# charge_controller_mk2.net
KiCad netlist of a schematic drawn in EAGLE
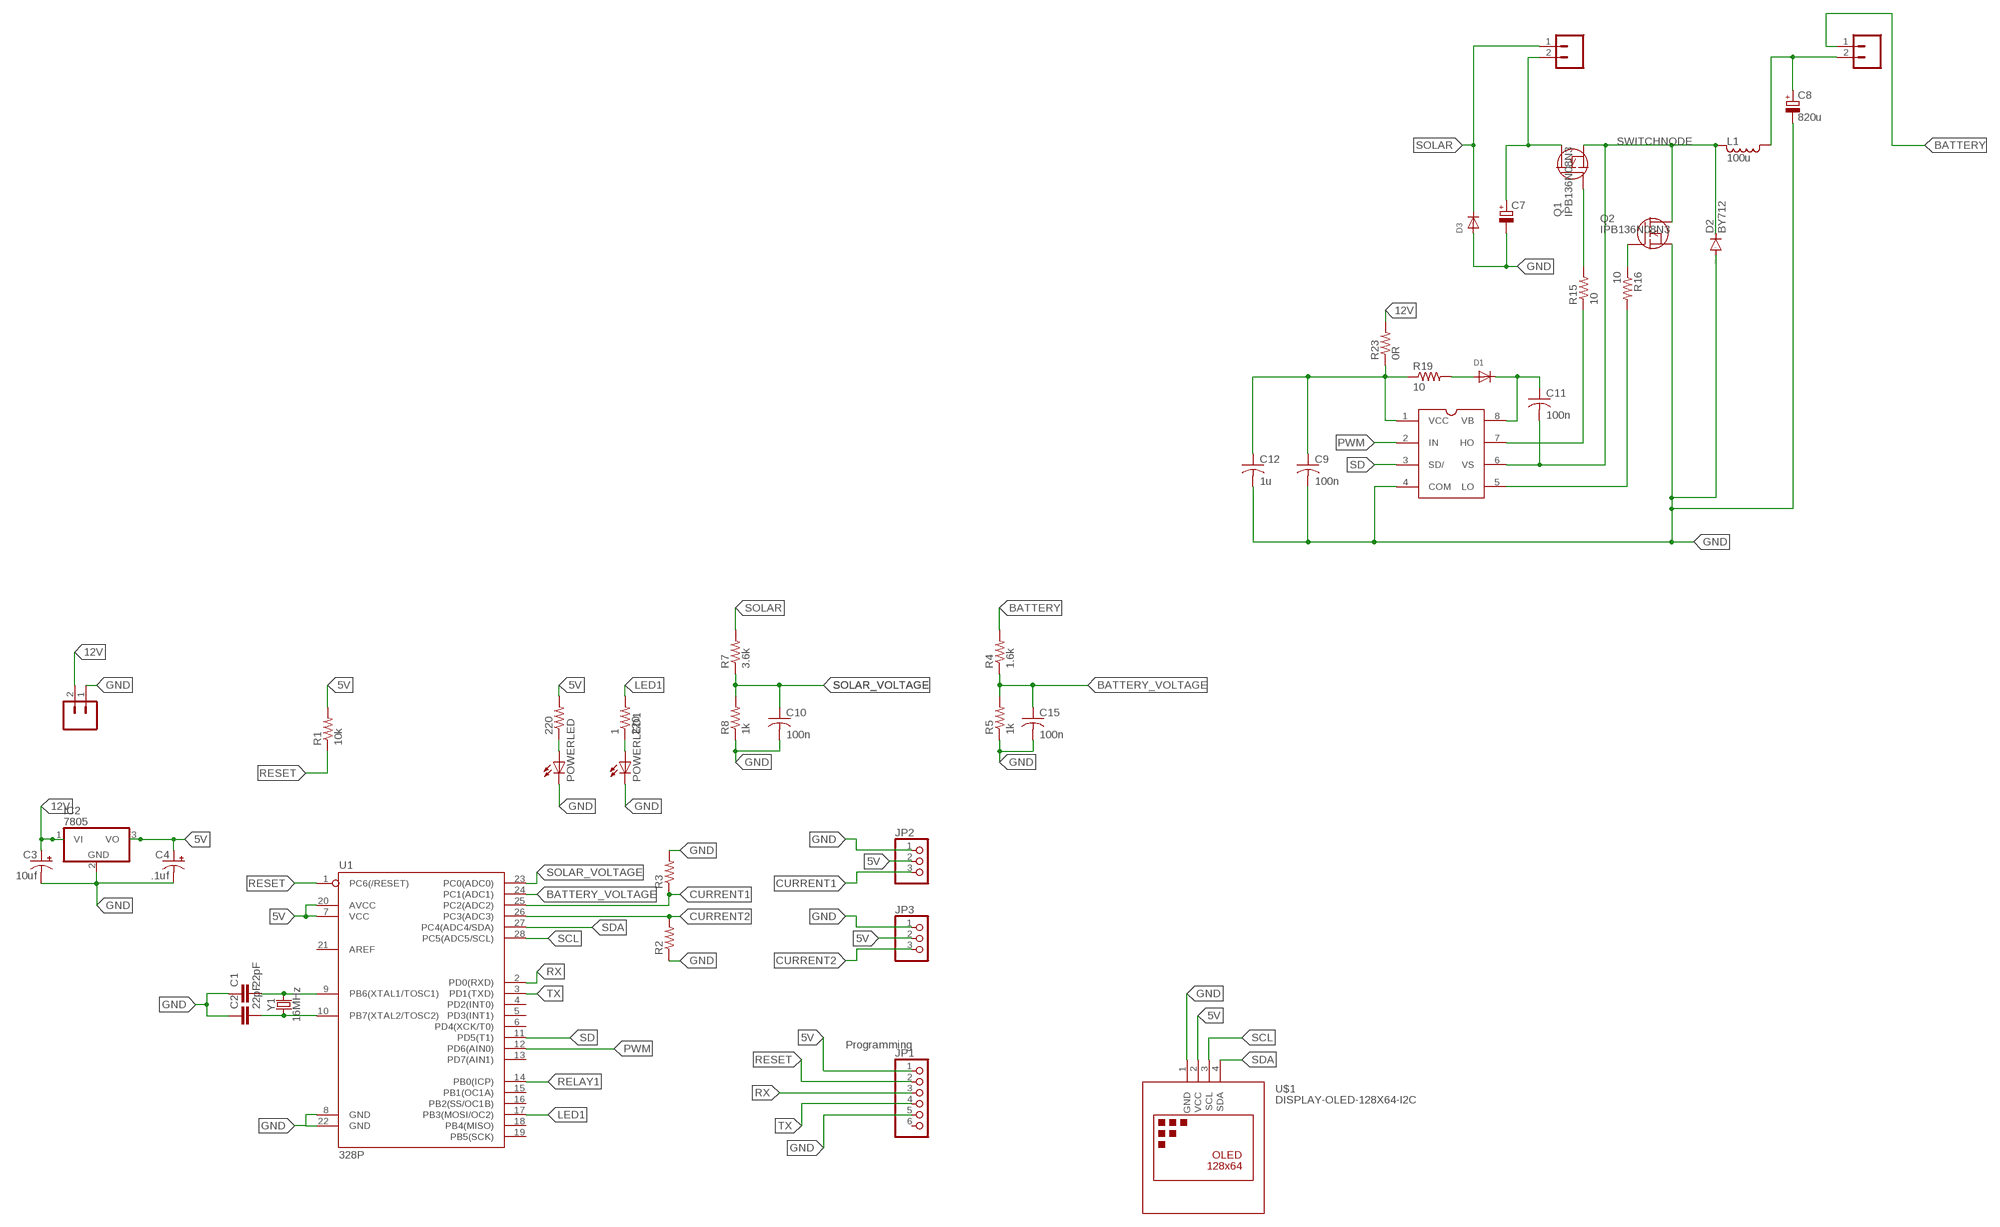
[diagram p0: schematic, sheet 1]

(export (version "E")
  (design (tool "Eeschema 10.0.6"))
  (components
    (comp (ref "1")
      (value "220")
      (footprint "eagle-import:0204_5")
      (libsource (lib "eagle-import") (part "adafruit_420_R-US_0204/5"))
    )
    (comp (ref "220")
      (value "R-US_0204/5")
      (footprint "eagle-import:0204_5")
      (libsource (lib "eagle-import") (part "adafruit_420_R-US_0204/5"))
    )
    (comp (ref "BATTERY-OUT")
      (value "CONN_025MM")
      (footprint "eagle-import:SCREWTERMINAL-5MM-2")
      (libsource (lib "eagle-import") (part "CONN_025MM"))
    )
    (comp (ref "C1")
      (value "22pF")
      (footprint "eagle-import:CAP-PTH-2.54")
      (libsource (lib "eagle-import") (part "22PF-PTH-2.54MM-200V-5%"))
    )
    (comp (ref "C2")
      (value "22pF")
      (footprint "eagle-import:CAP-PTH-2.54")
      (libsource (lib "eagle-import") (part "22PF-PTH-2.54MM-200V-5%"))
    )
    (comp (ref "C3")
      (value "10uf")
      (footprint "eagle-import:E5-5")
      (libsource (lib "eagle-import") (part "CPOL-USE5-5"))
    )
    (comp (ref "C4")
      (value ".1uf")
      (footprint "eagle-import:E5-5")
      (libsource (lib "eagle-import") (part "CPOL-USE5-5"))
    )
    (comp (ref "C7")
      (value "680u")
      (footprint "eagle-import:10MM")
      (libsource (lib "eagle-import") (part "C_POLARIZED10MM"))
    )
    (comp (ref "C8")
      (value "820u")
      (footprint "eagle-import:10MM")
      (libsource (lib "eagle-import") (part "C_POLARIZED10MM"))
    )
    (comp (ref "C9")
      (value "100n")
      (footprint "eagle-import:C050-025X075")
      (libsource (lib "eagle-import") (part "C-US050-025X075"))
    )
    (comp (ref "C10")
      (value "100n")
      (footprint "eagle-import:C050-025X075")
      (libsource (lib "eagle-import") (part "C-US050-025X075"))
    )
    (comp (ref "C11")
      (value "100n")
      (footprint "eagle-import:C050-055X075")
      (libsource (lib "eagle-import") (part "C-US050-055X075"))
    )
    (comp (ref "C12")
      (value "1u")
      (footprint "eagle-import:C050-025X075")
      (libsource (lib "eagle-import") (part "C-US050-025X075"))
    )
    (comp (ref "C15")
      (value "100n")
      (footprint "eagle-import:C050-025X075")
      (libsource (lib "eagle-import") (part "C-US050-025X075"))
    )
    (comp (ref "D1")
      (value "DIODEDO-1N4148")
      (footprint "eagle-import:DO-1N4148")
      (libsource (lib "eagle-import") (part "DIODEDO-1N4148"))
    )
    (comp (ref "D2")
      (value "BY712")
      (footprint "eagle-import:SOD61E")
      (libsource (lib "eagle-import") (part "BY712"))
    )
    (comp (ref "D3")
      (value "DIODEDO-1N4148")
      (footprint "eagle-import:DO-1N4148")
      (libsource (lib "eagle-import") (part "DIODEDO-1N4148"))
    )
    (comp (ref "IC2")
      (value "7805")
      (footprint "eagle-import:TO220V")
      (libsource (lib "eagle-import") (part "78TV18"))
    )
    (comp (ref "J1")
      (value "PWR_in")
      (footprint "eagle-import:SCREWTERMINAL-5MM-2")
      (libsource (lib "eagle-import") (part "CONN_025MM"))
    )
    (comp (ref "JP1")
      (value "PINHD-1X6")
      (footprint "eagle-import:1X06")
      (libsource (lib "eagle-import") (part "PINHD-1X6"))
    )
    (comp (ref "JP2")
      (value "PINHD-1X3")
      (footprint "eagle-import:1X03")
      (libsource (lib "eagle-import") (part "PINHD-1X3"))
    )
    (comp (ref "JP3")
      (value "PINHD-1X3")
      (footprint "eagle-import:1X03")
      (libsource (lib "eagle-import") (part "PINHD-1X3"))
    )
    (comp (ref "L1")
      (value "100u")
      (footprint "eagle-import:MSS1583")
      (libsource (lib "eagle-import") (part "INDUCTORMSS1583"))
    )
    (comp (ref "POWERLED")
      (value "LED5MM")
      (footprint "eagle-import:LED5MM")
      (libsource (lib "eagle-import") (part "LED5MM"))
    )
    (comp (ref "POWERLED1")
      (value "LED5MM")
      (footprint "eagle-import:LED5MM")
      (libsource (lib "eagle-import") (part "LED5MM"))
    )
    (comp (ref "Q1")
      (value "IPB136N08N3")
      (footprint "eagle-import:TO220")
      (libsource (lib "eagle-import") (part "IRF840"))
    )
    (comp (ref "Q2")
      (value "IPB136N08N3")
      (footprint "eagle-import:TO220")
      (libsource (lib "eagle-import") (part "IRF840"))
    )
    (comp (ref "R1")
      (value "10k")
      (footprint "eagle-import:0204_5")
      (libsource (lib "eagle-import") (part "adafruit_420_R-US_0204/5"))
    )
    (comp (ref "R2")
      (value "R-US_0207/7")
      (footprint "eagle-import:0207_7")
      (libsource (lib "eagle-import") (part "R-US_0207/7"))
    )
    (comp (ref "R3")
      (value "R-US_0207/7")
      (footprint "eagle-import:0207_7")
      (libsource (lib "eagle-import") (part "R-US_0207/7"))
    )
    (comp (ref "R4")
      (value "1.6k")
      (footprint "eagle-import:0207_7")
      (libsource (lib "eagle-import") (part "R-US_0207/7"))
    )
    (comp (ref "R5")
      (value "1k")
      (footprint "eagle-import:0207_7")
      (libsource (lib "eagle-import") (part "R-US_0207/7"))
    )
    (comp (ref "R7")
      (value "3.6k")
      (footprint "eagle-import:0207_7")
      (libsource (lib "eagle-import") (part "R-US_0207/7"))
    )
    (comp (ref "R8")
      (value "1k")
      (footprint "eagle-import:0207_7")
      (libsource (lib "eagle-import") (part "R-US_0207/7"))
    )
    (comp (ref "R15")
      (value "10")
      (footprint "eagle-import:0204_7")
      (libsource (lib "eagle-import") (part "adafruit_420_R-US_0204/7"))
    )
    (comp (ref "R16")
      (value "10")
      (footprint "eagle-import:0204_7")
      (libsource (lib "eagle-import") (part "adafruit_420_R-US_0204/7"))
    )
    (comp (ref "R19")
      (value "10")
      (footprint "eagle-import:0204_7")
      (libsource (lib "eagle-import") (part "adafruit_420_R-US_0204/7"))
    )
    (comp (ref "R23")
      (value "0R")
      (footprint "eagle-import:0204_7")
      (libsource (lib "eagle-import") (part "adafruit_420_R-US_0204/7"))
    )
    (comp (ref "SOLAR-IN")
      (value "CONN_025MM")
      (footprint "eagle-import:SCREWTERMINAL-5MM-2")
      (libsource (lib "eagle-import") (part "CONN_025MM"))
    )
    (comp (ref "U$1")
      (value "DISPLAY-OLED-128X64-I2C")
      (footprint "eagle-import:DISPLAY-OLED-128X64-I2C")
      (libsource (lib "eagle-import") (part "DISPLAY-OLED-128X64-I2C"))
    )
    (comp (ref "U$2")
      (value "IR2104")
      (footprint "eagle-import:IR2104")
      (libsource (lib "eagle-import") (part "IR2104"))
    )
    (comp (ref "U1")
      (value "328P")
      (footprint "eagle-import:DIP28")
      (libsource (lib "eagle-import") (part "ATMEGA328P_PDIP"))
    )
    (comp (ref "Y1")
      (value "16MHz")
      (footprint "eagle-import:HC49US")
      (libsource (lib "eagle-import") (part "CRYSTAL-16MHZPTH-HC49US"))
    )
  )
  (nets
    (net (code "1") (name "/SWITCHNODE") (class "Default")
      (node (ref "C11") (pin "2") (pinfunction "2_2") (pintype "passive"))
      (node (ref "D2") (pin "C") (pinfunction "C_C") (pintype "passive"))
      (node (ref "L1") (pin "2") (pinfunction "2_2") (pintype "passive"))
      (node (ref "Q1") (pin "3") (pinfunction "S_3") (pintype "passive"))
      (node (ref "Q2") (pin "2") (pinfunction "D_2") (pintype "passive"))
      (node (ref "U$2") (pin "6") (pinfunction "VS_6") (pintype "power_in"))
    )
    (net (code "2") (name "5V") (class "Default")
      (node (ref "220") (pin "2") (pinfunction "2_2") (pintype "passive"))
      (node (ref "C4") (pin "+") (pinfunction "+_+") (pintype "passive"))
      (node (ref "IC2") (pin "3") (pinfunction "VO_3") (pintype "passive"))
      (node (ref "JP1") (pin "1") (pinfunction "1_1") (pintype "passive"))
      (node (ref "JP2") (pin "2") (pinfunction "2_2") (pintype "passive"))
      (node (ref "JP3") (pin "2") (pinfunction "2_2") (pintype "passive"))
      (node (ref "R1") (pin "2") (pinfunction "2_2") (pintype "passive"))
      (node (ref "U$1") (pin "2") (pinfunction "VCC_2") (pintype "power_in"))
      (node (ref "U1") (pin "20") (pinfunction "AVCC_20") (pintype "bidirectional"))
      (node (ref "U1") (pin "7") (pinfunction "VCC_7") (pintype "bidirectional"))
    )
    (net (code "3") (name "12V") (class "Default")
      (node (ref "C3") (pin "+") (pinfunction "+_+") (pintype "passive"))
      (node (ref "IC2") (pin "1") (pinfunction "VI_1") (pintype "input"))
      (node (ref "J1") (pin "2") (pinfunction "2_2") (pintype "passive"))
      (node (ref "R23") (pin "2") (pinfunction "2_2") (pintype "passive"))
    )
    (net (code "4") (name "BATTERY") (class "Default")
      (node (ref "BATTERY-OUT") (pin "1") (pinfunction "1_1") (pintype "passive"))
      (node (ref "R4") (pin "2") (pinfunction "2_2") (pintype "passive"))
    )
    (net (code "5") (name "BATTERY_VOLTAGE") (class "Default")
      (node (ref "C15") (pin "1") (pinfunction "1_1") (pintype "passive"))
      (node (ref "R4") (pin "1") (pinfunction "1_1") (pintype "passive"))
      (node (ref "R5") (pin "2") (pinfunction "2_2") (pintype "passive"))
      (node (ref "U1") (pin "24") (pinfunction "PC1(ADC1)_24") (pintype "bidirectional"))
    )
    (net (code "6") (name "CURRENT1") (class "Default")
      (node (ref "JP2") (pin "3") (pinfunction "3_3") (pintype "passive"))
      (node (ref "R3") (pin "1") (pinfunction "1_1") (pintype "passive"))
      (node (ref "U1") (pin "25") (pinfunction "PC2(ADC2)_25") (pintype "bidirectional"))
    )
    (net (code "7") (name "CURRENT2") (class "Default")
      (node (ref "JP3") (pin "3") (pinfunction "3_3") (pintype "passive"))
      (node (ref "R2") (pin "2") (pinfunction "2_2") (pintype "passive"))
      (node (ref "U1") (pin "26") (pinfunction "PC3(ADC3)_26") (pintype "bidirectional"))
    )
    (net (code "8") (name "GND") (class "Default")
      (node (ref "C1") (pin "1") (pinfunction "1_1") (pintype "passive"))
      (node (ref "C10") (pin "2") (pinfunction "2_2") (pintype "passive"))
      (node (ref "C12") (pin "2") (pinfunction "2_2") (pintype "passive"))
      (node (ref "C15") (pin "2") (pinfunction "2_2") (pintype "passive"))
      (node (ref "C2") (pin "1") (pinfunction "1_1") (pintype "passive"))
      (node (ref "C3") (pin "-") (pinfunction "-_-") (pintype "passive"))
      (node (ref "C4") (pin "-") (pinfunction "-_-") (pintype "passive"))
      (node (ref "C7") (pin "-") (pinfunction "-_-") (pintype "passive"))
      (node (ref "C8") (pin "-") (pinfunction "-_-") (pintype "passive"))
      (node (ref "C9") (pin "2") (pinfunction "2_2") (pintype "passive"))
      (node (ref "D2") (pin "A") (pinfunction "A_A") (pintype "passive"))
      (node (ref "D3") (pin "A") (pinfunction "A_A") (pintype "passive"))
      (node (ref "IC2") (pin "2") (pinfunction "GND_2") (pintype "passive"))
      (node (ref "J1") (pin "1") (pinfunction "1_1") (pintype "passive"))
      (node (ref "JP1") (pin "5") (pinfunction "5_5") (pintype "passive"))
      (node (ref "JP2") (pin "1") (pinfunction "1_1") (pintype "passive"))
      (node (ref "JP3") (pin "1") (pinfunction "1_1") (pintype "passive"))
      (node (ref "POWERLED") (pin "K") (pinfunction "C_K") (pintype "passive"))
      (node (ref "POWERLED1") (pin "K") (pinfunction "C_K") (pintype "passive"))
      (node (ref "Q2") (pin "3") (pinfunction "S_3") (pintype "passive"))
      (node (ref "R2") (pin "1") (pinfunction "1_1") (pintype "passive"))
      (node (ref "R3") (pin "2") (pinfunction "2_2") (pintype "passive"))
      (node (ref "R5") (pin "1") (pinfunction "1_1") (pintype "passive"))
      (node (ref "R8") (pin "1") (pinfunction "1_1") (pintype "passive"))
      (node (ref "U$1") (pin "1") (pinfunction "GND_1") (pintype "power_in"))
      (node (ref "U$2") (pin "4") (pinfunction "COM_4") (pintype "bidirectional"))
      (node (ref "U1") (pin "22") (pinfunction "GND_22") (pintype "bidirectional"))
      (node (ref "U1") (pin "8") (pinfunction "GND_8") (pintype "bidirectional"))
    )
    (net (code "9") (name "LED1") (class "Default")
      (node (ref "1") (pin "2") (pinfunction "2_2") (pintype "passive"))
      (node (ref "U1") (pin "17") (pinfunction "PB3(MOSI/OC2)_17") (pintype "bidirectional"))
    )
    (net (code "10") (name "Net-(1-Pad1)") (class "Default")
      (node (ref "1") (pin "1") (pinfunction "1_1") (pintype "passive"))
      (node (ref "POWERLED1") (pin "A") (pinfunction "A_A") (pintype "passive"))
    )
    (net (code "11") (name "Net-(220-Pad1)") (class "Default")
      (node (ref "220") (pin "1") (pinfunction "1_1") (pintype "passive"))
      (node (ref "POWERLED") (pin "A") (pinfunction "A_A") (pintype "passive"))
    )
    (net (code "12") (name "Net-(BATTERY-OUT-Pad2)") (class "Default")
      (node (ref "BATTERY-OUT") (pin "2") (pinfunction "2_2") (pintype "passive"))
      (node (ref "C8") (pin "+") (pinfunction "+_+") (pintype "passive"))
      (node (ref "L1") (pin "1") (pinfunction "1_1") (pintype "passive"))
    )
    (net (code "13") (name "Net-(D1-PadA)") (class "Default")
      (node (ref "D1") (pin "A") (pinfunction "A_A") (pintype "passive"))
      (node (ref "R19") (pin "2") (pinfunction "2_2") (pintype "passive"))
    )
    (net (code "14") (name "Net-(Q1-D)") (class "Default")
      (node (ref "C7") (pin "+") (pinfunction "+_+") (pintype "passive"))
      (node (ref "Q1") (pin "2") (pinfunction "D_2") (pintype "passive"))
      (node (ref "SOLAR-IN") (pin "2") (pinfunction "2_2") (pintype "passive"))
    )
    (net (code "15") (name "Net-(Q1-G)") (class "Default")
      (node (ref "Q1") (pin "1") (pinfunction "G_1") (pintype "passive"))
      (node (ref "R15") (pin "2") (pinfunction "2_2") (pintype "passive"))
    )
    (net (code "16") (name "Net-(Q2-G)") (class "Default")
      (node (ref "Q2") (pin "1") (pinfunction "G_1") (pintype "passive"))
      (node (ref "R16") (pin "1") (pinfunction "1_1") (pintype "passive"))
    )
    (net (code "17") (name "Net-(U$2-HO)") (class "Default")
      (node (ref "R15") (pin "1") (pinfunction "1_1") (pintype "passive"))
      (node (ref "U$2") (pin "7") (pinfunction "HO_7") (pintype "bidirectional"))
    )
    (net (code "18") (name "Net-(U$2-LO)") (class "Default")
      (node (ref "R16") (pin "2") (pinfunction "2_2") (pintype "passive"))
      (node (ref "U$2") (pin "5") (pinfunction "LO_5") (pintype "bidirectional"))
    )
    (net (code "19") (name "Net-(U$2-VB)") (class "Default")
      (node (ref "C11") (pin "1") (pinfunction "1_1") (pintype "passive"))
      (node (ref "D1") (pin "C") (pinfunction "C_C") (pintype "passive"))
      (node (ref "U$2") (pin "8") (pinfunction "VB_8") (pintype "power_in"))
    )
    (net (code "20") (name "Net-(U$2-VCC)") (class "Default")
      (node (ref "C12") (pin "1") (pinfunction "1_1") (pintype "passive"))
      (node (ref "C9") (pin "1") (pinfunction "1_1") (pintype "passive"))
      (node (ref "R19") (pin "1") (pinfunction "1_1") (pintype "passive"))
      (node (ref "R23") (pin "1") (pinfunction "1_1") (pintype "passive"))
      (node (ref "U$2") (pin "1") (pinfunction "VCC_1") (pintype "power_in"))
    )
    (net (code "21") (name "Net-(U1-PB6(XTAL1{slash}TOSC1))") (class "Default")
      (node (ref "C1") (pin "2") (pinfunction "2_2") (pintype "passive"))
      (node (ref "U1") (pin "9") (pinfunction "PB6(XTAL1/TOSC1)_9") (pintype "bidirectional"))
      (node (ref "Y1") (pin "2") (pinfunction "2_2") (pintype "passive"))
    )
    (net (code "22") (name "Net-(U1-PB7(XTAL2{slash}TOSC2))") (class "Default")
      (node (ref "C2") (pin "2") (pinfunction "2_2") (pintype "passive"))
      (node (ref "U1") (pin "10") (pinfunction "PB7(XTAL2/TOSC2)_10") (pintype "bidirectional"))
      (node (ref "Y1") (pin "1") (pinfunction "1_1") (pintype "passive"))
    )
    (net (code "23") (name "PWM") (class "Default")
      (node (ref "U$2") (pin "2") (pinfunction "IN_2") (pintype "bidirectional"))
      (node (ref "U1") (pin "12") (pinfunction "PD6(AIN0)_12") (pintype "bidirectional"))
    )
    (net (code "24") (name "RELAY1") (class "Default")
      (node (ref "U1") (pin "14") (pinfunction "PB0(ICP)_14") (pintype "bidirectional"))
    )
    (net (code "25") (name "RESET") (class "Default")
      (node (ref "JP1") (pin "2") (pinfunction "2_2") (pintype "passive"))
      (node (ref "R1") (pin "1") (pinfunction "1_1") (pintype "passive"))
      (node (ref "U1") (pin "1") (pinfunction "PC6(/RESET)_1") (pintype "bidirectional"))
    )
    (net (code "26") (name "RX") (class "Default")
      (node (ref "JP1") (pin "3") (pinfunction "3_3") (pintype "passive"))
      (node (ref "U1") (pin "2") (pinfunction "PD0(RXD)_2") (pintype "bidirectional"))
    )
    (net (code "27") (name "SCL") (class "Default")
      (node (ref "U$1") (pin "3") (pinfunction "SCL_3") (pintype "bidirectional"))
      (node (ref "U1") (pin "28") (pinfunction "PC5(ADC5/SCL)_28") (pintype "bidirectional"))
    )
    (net (code "28") (name "SD") (class "Default")
      (node (ref "U$2") (pin "3") (pinfunction "SD/_3") (pintype "bidirectional"))
      (node (ref "U1") (pin "11") (pinfunction "PD5(T1)_11") (pintype "bidirectional"))
    )
    (net (code "29") (name "SDA") (class "Default")
      (node (ref "U$1") (pin "4") (pinfunction "SDA_4") (pintype "bidirectional"))
      (node (ref "U1") (pin "27") (pinfunction "PC4(ADC4/SDA)_27") (pintype "bidirectional"))
    )
    (net (code "30") (name "SOLAR") (class "Default")
      (node (ref "D3") (pin "C") (pinfunction "C_C") (pintype "passive"))
      (node (ref "R7") (pin "2") (pinfunction "2_2") (pintype "passive"))
      (node (ref "SOLAR-IN") (pin "1") (pinfunction "1_1") (pintype "passive"))
    )
    (net (code "31") (name "SOLAR_VOLTAGE") (class "Default")
      (node (ref "C10") (pin "1") (pinfunction "1_1") (pintype "passive"))
      (node (ref "R7") (pin "1") (pinfunction "1_1") (pintype "passive"))
      (node (ref "R8") (pin "2") (pinfunction "2_2") (pintype "passive"))
      (node (ref "U1") (pin "23") (pinfunction "PC0(ADC0)_23") (pintype "bidirectional"))
    )
    (net (code "32") (name "TX") (class "Default")
      (node (ref "JP1") (pin "4") (pinfunction "4_4") (pintype "passive"))
      (node (ref "U1") (pin "3") (pinfunction "PD1(TXD)_3") (pintype "bidirectional"))
    )
    (net (code "33") (name "unconnected-(JP1-Pad6)") (class "Default")
      (node (ref "JP1") (pin "6") (pinfunction "6_6") (pintype "passive"))
    )
    (net (code "34") (name "unconnected-(U1-AREF-Pad21)") (class "Default")
      (node (ref "U1") (pin "21") (pinfunction "AREF_21") (pintype "bidirectional"))
    )
    (net (code "35") (name "unconnected-(U1-PB1(OC1A)-Pad15)") (class "Default")
      (node (ref "U1") (pin "15") (pinfunction "PB1(OC1A)_15") (pintype "bidirectional"))
    )
    (net (code "36") (name "unconnected-(U1-PB2(SS{slash}OC1B)-Pad16)") (class "Default")
      (node (ref "U1") (pin "16") (pinfunction "PB2(SS/OC1B)_16") (pintype "bidirectional"))
    )
    (net (code "37") (name "unconnected-(U1-PB4(MISO)-Pad18)") (class "Default")
      (node (ref "U1") (pin "18") (pinfunction "PB4(MISO)_18") (pintype "bidirectional"))
    )
    (net (code "38") (name "unconnected-(U1-PB5(SCK)-Pad19)") (class "Default")
      (node (ref "U1") (pin "19") (pinfunction "PB5(SCK)_19") (pintype "bidirectional"))
    )
    (net (code "39") (name "unconnected-(U1-PD2(INT0)-Pad4)") (class "Default")
      (node (ref "U1") (pin "4") (pinfunction "PD2(INT0)_4") (pintype "bidirectional"))
    )
    (net (code "40") (name "unconnected-(U1-PD3(INT1)-Pad5)") (class "Default")
      (node (ref "U1") (pin "5") (pinfunction "PD3(INT1)_5") (pintype "bidirectional"))
    )
    (net (code "41") (name "unconnected-(U1-PD4(XCK{slash}T0)-Pad6)") (class "Default")
      (node (ref "U1") (pin "6") (pinfunction "PD4(XCK/T0)_6") (pintype "bidirectional"))
    )
    (net (code "42") (name "unconnected-(U1-PD7(AIN1)-Pad13)") (class "Default")
      (node (ref "U1") (pin "13") (pinfunction "PD7(AIN1)_13") (pintype "bidirectional"))
    )
  )
)
